# PowerSupply.net
KiCad netlist of a schematic drawn in Altium Designer
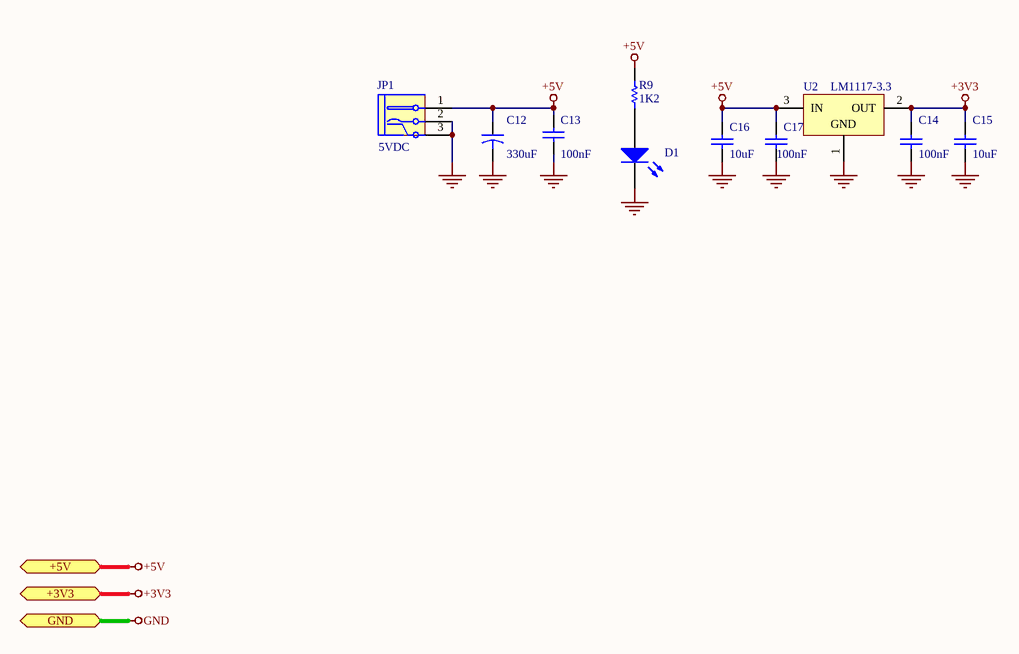
[diagram p0: PowerSupply.SchDoc]

(export (version "E")
  (design (tool "Eeschema 10.0.6"))
  (components
    (comp (ref "C12")
      (value "330uF")
      (footprint "C-ALU-10x10.2mm")
      (description "100UF 50V 10x10.2MM")
      (fields (field (name "Comment") "330uF/50V") (field (name "PUBLISHER") "Altium Limited"))
      (libsource (lib "Miscellaneous Devices") (part "Cap2"))
    )
    (comp (ref "C13")
      (value "100nF")
      (footprint "C-0805")
      (description "Capacitor")
      (fields (field (name "Comment") "104") (field (name "PUBLISHER") "Altium Limited"))
      (libsource (lib "Miscellaneous Devices") (part "Cap"))
    )
    (comp (ref "C14")
      (value "100nF")
      (footprint "C-0805")
      (description "Capacitor")
      (fields (field (name "Comment") "104") (field (name "PUBLISHER") "Altium Limited"))
      (libsource (lib "Miscellaneous Devices") (part "Cap"))
    )
    (comp (ref "C15")
      (value "10uF")
      (footprint "C-0805")
      (description "Capacitor")
      (fields (field (name "Comment") "106") (field (name "PUBLISHER") "Altium Limited"))
      (libsource (lib "Miscellaneous Devices") (part "Cap"))
    )
    (comp (ref "C16")
      (value "10uF")
      (footprint "C-0805")
      (description "Capacitor")
      (fields (field (name "Comment") "106") (field (name "PUBLISHER") "Altium Limited"))
      (libsource (lib "Miscellaneous Devices") (part "Cap"))
    )
    (comp (ref "C17")
      (value "100nF")
      (footprint "C-0805")
      (description "Capacitor")
      (fields (field (name "Comment") "104") (field (name "PUBLISHER") "Altium Limited"))
      (libsource (lib "Miscellaneous Devices") (part "Cap"))
    )
    (comp (ref "D1")
      (value "SMD0805-RED")
      (footprint "LED-0805")
      (description "Typical INFRARED GaAs LED")
      (libsource (lib "Miscellaneous Devices") (part "LED0"))
    )
    (comp (ref "JP1")
      (value "5VDC")
      (footprint "TER-JACKDC-5.5x2.1mm")
      (description "Jack DC5.5x2.5MM DC5525")
      (fields (field (name "Comment") "JackDC5.5x2.5"))
      (libsource (lib "Dlib") (part "JACK DC12V"))
    )
    (comp (ref "R9")
      (value "1K2")
      (footprint "R-0805")
      (description "Resistor")
      (fields (field (name "PUBLISHER") "Altium Limited"))
      (libsource (lib "Miscellaneous Devices") (part "Res1"))
    )
    (comp (ref "U2")
      (value "LM1117-3.3")
      (footprint "SOT-223-3")
      (description "800mA Low-Dropout Linear Regulator, 3-pin TO-252")
      (fields
        (field (name "PARTNUMBER") "LM1117DT-3.3")
        (field (name "MANUFACTURER") "National Semiconductor")
        (field (name "PUBLISHER") "Altium Limited")
      )
      (libsource (lib "NSC LDO") (part "LM1117DT-3.3"))
    )
  )
  (nets
    (net (code "1") (name "+3V3") (class "Default")
      (node (ref "C14") (pin "1") (pinfunction "1_1") (pintype "passive"))
      (node (ref "C15") (pin "1") (pinfunction "1_1") (pintype "passive"))
      (node (ref "U2") (pin "2") (pinfunction "OUT_2") (pintype "power_in"))
    )
    (net (code "2") (name "+5V") (class "Default")
      (node (ref "C12") (pin "1") (pinfunction "1_1") (pintype "passive"))
      (node (ref "C13") (pin "1") (pinfunction "1_1") (pintype "passive"))
      (node (ref "C16") (pin "1") (pinfunction "1_1") (pintype "passive"))
      (node (ref "C17") (pin "1") (pinfunction "1_1") (pintype "passive"))
      (node (ref "JP1") (pin "1") (pinfunction "T_1") (pintype "passive"))
      (node (ref "R9") (pin "2") (pinfunction "2_2") (pintype "passive"))
      (node (ref "U2") (pin "3") (pinfunction "IN_3") (pintype "power_in"))
    )
    (net (code "3") (name "GND") (class "Default")
      (node (ref "C12") (pin "2") (pinfunction "2_2") (pintype "passive"))
      (node (ref "C13") (pin "2") (pinfunction "2_2") (pintype "passive"))
      (node (ref "C14") (pin "2") (pinfunction "2_2") (pintype "passive"))
      (node (ref "C15") (pin "2") (pinfunction "2_2") (pintype "passive"))
      (node (ref "C16") (pin "2") (pinfunction "2_2") (pintype "passive"))
      (node (ref "C17") (pin "2") (pinfunction "2_2") (pintype "passive"))
      (node (ref "D1") (pin "2") (pinfunction "K_2") (pintype "passive"))
      (node (ref "JP1") (pin "2") (pinfunction "TN_2") (pintype "passive"))
      (node (ref "JP1") (pin "3") (pinfunction "S_3") (pintype "power_in"))
      (node (ref "U2") (pin "1") (pinfunction "GND_1") (pintype "power_in"))
    )
    (net (code "4") (name "Net-(D1-A)") (class "Default")
      (node (ref "D1") (pin "1") (pinfunction "A_1") (pintype "passive"))
      (node (ref "R9") (pin "1") (pinfunction "1_1") (pintype "passive"))
    )
  )
)
